# board.net
KiCad netlist of a schematic drawn in EAGLE
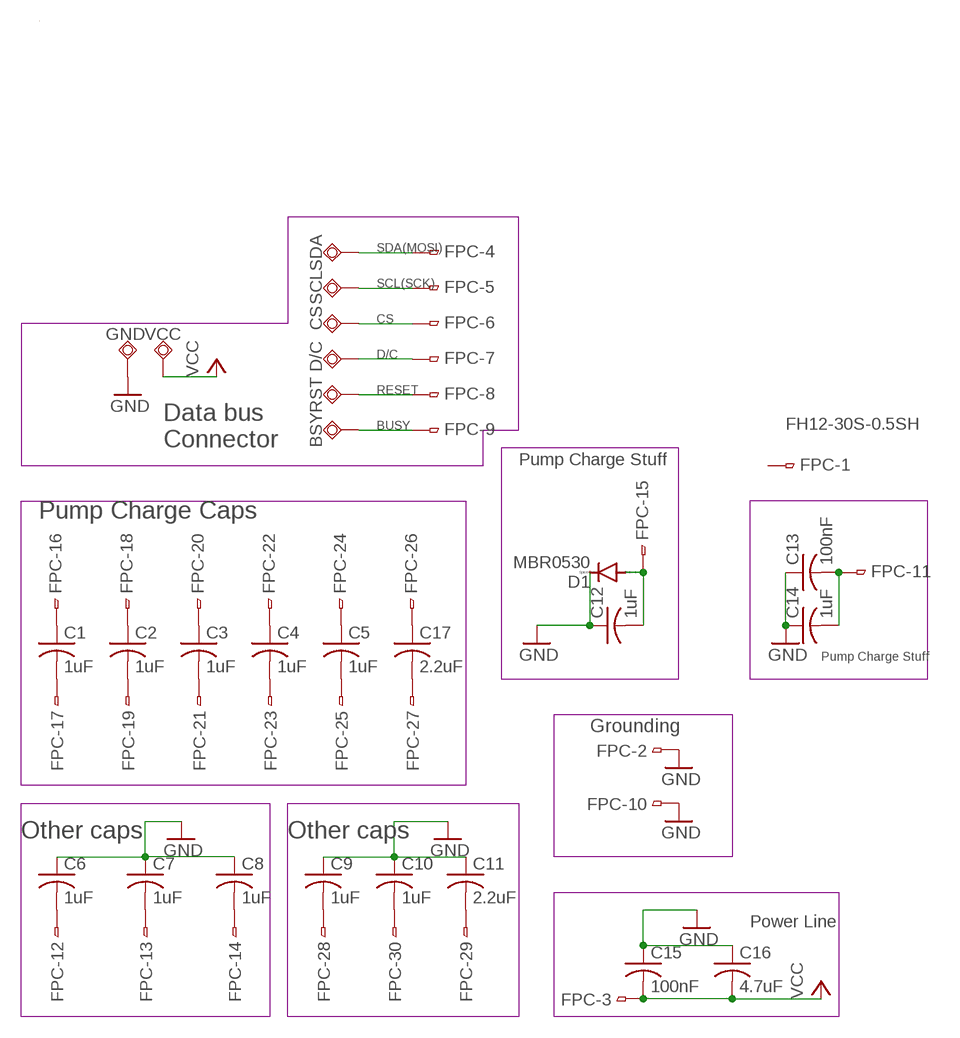
[diagram p0: schematic, sheet 1]

(export (version "E")
  (design (tool "Eeschema 10.0.6"))
  (components
    (comp (ref "BSY")
      (value "TPSQTP18SQ")
      (footprint "eagle-import:TP18SQ")
      (libsource (lib "eagle-import") (part "TPSQTP18SQ"))
    )
    (comp (ref "C1")
      (value "1uF")
      (footprint "eagle-import:C0805")
      (libsource (lib "eagle-import") (part "C-USC0805"))
    )
    (comp (ref "C2")
      (value "1uF")
      (footprint "eagle-import:C0805")
      (libsource (lib "eagle-import") (part "C-USC0805"))
    )
    (comp (ref "C3")
      (value "1uF")
      (footprint "eagle-import:C0805")
      (libsource (lib "eagle-import") (part "C-USC0805"))
    )
    (comp (ref "C4")
      (value "1uF")
      (footprint "eagle-import:C0805")
      (libsource (lib "eagle-import") (part "C-USC0805"))
    )
    (comp (ref "C5")
      (value "1uF")
      (footprint "eagle-import:C0805")
      (libsource (lib "eagle-import") (part "C-USC0805"))
    )
    (comp (ref "C6")
      (value "1uF")
      (footprint "eagle-import:C0805")
      (libsource (lib "eagle-import") (part "C-USC0805"))
    )
    (comp (ref "C7")
      (value "1uF")
      (footprint "eagle-import:C0805")
      (libsource (lib "eagle-import") (part "C-USC0805"))
    )
    (comp (ref "C8")
      (value "1uF")
      (footprint "eagle-import:C0805")
      (libsource (lib "eagle-import") (part "C-USC0805"))
    )
    (comp (ref "C9")
      (value "1uF")
      (footprint "eagle-import:C0805")
      (libsource (lib "eagle-import") (part "C-USC0805"))
    )
    (comp (ref "C10")
      (value "1uF")
      (footprint "eagle-import:C0805")
      (libsource (lib "eagle-import") (part "C-USC0805"))
    )
    (comp (ref "C11")
      (value "2.2uF")
      (footprint "eagle-import:C1206")
      (libsource (lib "eagle-import") (part "C-USC1206"))
    )
    (comp (ref "C12")
      (value "1uF")
      (footprint "eagle-import:C0805")
      (libsource (lib "eagle-import") (part "C-USC0805"))
    )
    (comp (ref "C13")
      (value "100nF")
      (footprint "eagle-import:C0805")
      (libsource (lib "eagle-import") (part "C-USC0805"))
    )
    (comp (ref "C14")
      (value "1uF")
      (footprint "eagle-import:C0805")
      (libsource (lib "eagle-import") (part "C-USC0805"))
    )
    (comp (ref "C15")
      (value "100nF")
      (footprint "eagle-import:C0805")
      (libsource (lib "eagle-import") (part "C-USC0805"))
    )
    (comp (ref "C16")
      (value "4.7uF")
      (footprint "eagle-import:C0805")
      (libsource (lib "eagle-import") (part "C-USC0805"))
    )
    (comp (ref "C17")
      (value "2.2uF")
      (footprint "eagle-import:C1206")
      (libsource (lib "eagle-import") (part "C-USC1206"))
    )
    (comp (ref "CS")
      (value "TPSQTP18SQ")
      (footprint "eagle-import:TP18SQ")
      (libsource (lib "eagle-import") (part "TPSQTP18SQ"))
    )
    (comp (ref "D/C")
      (value "TPSQTP18SQ")
      (footprint "eagle-import:TP18SQ")
      (libsource (lib "eagle-import") (part "TPSQTP18SQ"))
    )
    (comp (ref "D1")
      (value "MBR0530")
      (footprint "eagle-import:SOD-123_MINI-SMA")
      (libsource (lib "eagle-import") (part "CGRM400-G1"))
    )
    (comp (ref "FPC")
      (value "FH12-30S-0.5SH")
      (footprint "eagle-import:FH12-30S-0.5SH")
      (fields (field (name "MPN") "FH12-30S-0.5SH(55)"))
      (libsource (lib "eagle-import") (part "FH12-30S-0.5SH"))
    )
    (comp (ref "GND")
      (value "TPSQTP18SQ")
      (footprint "eagle-import:TP18SQ")
      (libsource (lib "eagle-import") (part "TPSQTP18SQ"))
    )
    (comp (ref "RST")
      (value "TPSQTP18SQ")
      (footprint "eagle-import:TP18SQ")
      (libsource (lib "eagle-import") (part "TPSQTP18SQ"))
    )
    (comp (ref "SCL")
      (value "TPSQTP18SQ")
      (footprint "eagle-import:TP18SQ")
      (libsource (lib "eagle-import") (part "TPSQTP18SQ"))
    )
    (comp (ref "SDA")
      (value "TPSQTP18SQ")
      (footprint "eagle-import:TP18SQ")
      (libsource (lib "eagle-import") (part "TPSQTP18SQ"))
    )
    (comp (ref "VCC")
      (value "TPSQTP18SQ")
      (footprint "eagle-import:TP18SQ")
      (libsource (lib "eagle-import") (part "TPSQTP18SQ"))
    )
  )
  (nets
    (net (code "1") (name "/BUSY") (class "Default")
      (node (ref "BSY") (pin "TP") (pinfunction "TP_TP") (pintype "input"))
      (node (ref "FPC") (pin "9") (pinfunction "1_9") (pintype "passive"))
    )
    (net (code "2") (name "/CS") (class "Default")
      (node (ref "CS") (pin "TP") (pinfunction "TP_TP") (pintype "input"))
      (node (ref "FPC") (pin "6") (pinfunction "1_6") (pintype "passive"))
    )
    (net (code "3") (name "/D{slash}C") (class "Default")
      (node (ref "D/C") (pin "TP") (pinfunction "TP_TP") (pintype "input"))
      (node (ref "FPC") (pin "7") (pinfunction "1_7") (pintype "passive"))
    )
    (net (code "4") (name "/RESET") (class "Default")
      (node (ref "FPC") (pin "8") (pinfunction "1_8") (pintype "passive"))
      (node (ref "RST") (pin "TP") (pinfunction "TP_TP") (pintype "input"))
    )
    (net (code "5") (name "/SCL(SCK)") (class "Default")
      (node (ref "FPC") (pin "5") (pinfunction "1_5") (pintype "passive"))
      (node (ref "SCL") (pin "TP") (pinfunction "TP_TP") (pintype "input"))
    )
    (net (code "6") (name "/SDA(MOSI)") (class "Default")
      (node (ref "FPC") (pin "4") (pinfunction "1_4") (pintype "passive"))
      (node (ref "SDA") (pin "TP") (pinfunction "TP_TP") (pintype "input"))
    )
    (net (code "7") (name "GND") (class "Default")
      (node (ref "C10") (pin "1") (pinfunction "1_1") (pintype "passive"))
      (node (ref "C11") (pin "1") (pinfunction "1_1") (pintype "passive"))
      (node (ref "C12") (pin "1") (pinfunction "1_1") (pintype "passive"))
      (node (ref "C13") (pin "1") (pinfunction "1_1") (pintype "passive"))
      (node (ref "C14") (pin "1") (pinfunction "1_1") (pintype "passive"))
      (node (ref "C15") (pin "1") (pinfunction "1_1") (pintype "passive"))
      (node (ref "C16") (pin "1") (pinfunction "1_1") (pintype "passive"))
      (node (ref "C6") (pin "1") (pinfunction "1_1") (pintype "passive"))
      (node (ref "C7") (pin "1") (pinfunction "1_1") (pintype "passive"))
      (node (ref "C8") (pin "1") (pinfunction "1_1") (pintype "passive"))
      (node (ref "C9") (pin "1") (pinfunction "1_1") (pintype "passive"))
      (node (ref "D1") (pin "C") (pinfunction "C_C") (pintype "passive"))
      (node (ref "FPC") (pin "10") (pinfunction "1_10") (pintype "passive"))
      (node (ref "FPC") (pin "2") (pinfunction "1_2") (pintype "passive"))
      (node (ref "GND") (pin "TP") (pinfunction "TP_TP") (pintype "input"))
    )
    (net (code "8") (name "Net-(FPCC-1)") (class "Default")
      (node (ref "C13") (pin "2") (pinfunction "2_2") (pintype "passive"))
      (node (ref "C14") (pin "2") (pinfunction "2_2") (pintype "passive"))
      (node (ref "FPC") (pin "11") (pinfunction "1_11") (pintype "passive"))
    )
    (net (code "9") (name "Net-(FPCD-1)") (class "Default")
      (node (ref "C6") (pin "2") (pinfunction "2_2") (pintype "passive"))
      (node (ref "FPC") (pin "12") (pinfunction "1_12") (pintype "passive"))
    )
    (net (code "10") (name "Net-(FPCE-1)") (class "Default")
      (node (ref "C7") (pin "2") (pinfunction "2_2") (pintype "passive"))
      (node (ref "FPC") (pin "13") (pinfunction "1_13") (pintype "passive"))
    )
    (net (code "11") (name "Net-(FPCF-1)") (class "Default")
      (node (ref "C8") (pin "2") (pinfunction "2_2") (pintype "passive"))
      (node (ref "FPC") (pin "14") (pinfunction "1_14") (pintype "passive"))
    )
    (net (code "12") (name "Net-(FPCG-1)") (class "Default")
      (node (ref "C12") (pin "2") (pinfunction "2_2") (pintype "passive"))
      (node (ref "D1") (pin "A") (pinfunction "A_A") (pintype "passive"))
      (node (ref "FPC") (pin "15") (pinfunction "1_15") (pintype "passive"))
    )
    (net (code "13") (name "Net-(FPCH-1)") (class "Default")
      (node (ref "C1") (pin "1") (pinfunction "1_1") (pintype "passive"))
      (node (ref "FPC") (pin "16") (pinfunction "1_16") (pintype "passive"))
    )
    (net (code "14") (name "Net-(FPCI-1)") (class "Default")
      (node (ref "C1") (pin "2") (pinfunction "2_2") (pintype "passive"))
      (node (ref "FPC") (pin "17") (pinfunction "1_17") (pintype "passive"))
    )
    (net (code "15") (name "Net-(FPCJ-1)") (class "Default")
      (node (ref "C2") (pin "1") (pinfunction "1_1") (pintype "passive"))
      (node (ref "FPC") (pin "18") (pinfunction "1_18") (pintype "passive"))
    )
    (net (code "16") (name "Net-(FPCK-1)") (class "Default")
      (node (ref "C2") (pin "2") (pinfunction "2_2") (pintype "passive"))
      (node (ref "FPC") (pin "19") (pinfunction "1_19") (pintype "passive"))
    )
    (net (code "17") (name "Net-(FPCM-1)") (class "Default")
      (node (ref "C3") (pin "1") (pinfunction "1_1") (pintype "passive"))
      (node (ref "FPC") (pin "20") (pinfunction "1_20") (pintype "passive"))
    )
    (net (code "18") (name "Net-(FPCN-1)") (class "Default")
      (node (ref "C3") (pin "2") (pinfunction "2_2") (pintype "passive"))
      (node (ref "FPC") (pin "21") (pinfunction "1_21") (pintype "passive"))
    )
    (net (code "19") (name "Net-(FPCO-1)") (class "Default")
      (node (ref "C4") (pin "1") (pinfunction "1_1") (pintype "passive"))
      (node (ref "FPC") (pin "22") (pinfunction "1_22") (pintype "passive"))
    )
    (net (code "20") (name "Net-(FPCP-1)") (class "Default")
      (node (ref "C4") (pin "2") (pinfunction "2_2") (pintype "passive"))
      (node (ref "FPC") (pin "23") (pinfunction "1_23") (pintype "passive"))
    )
    (net (code "21") (name "Net-(FPCQ-1)") (class "Default")
      (node (ref "C5") (pin "1") (pinfunction "1_1") (pintype "passive"))
      (node (ref "FPC") (pin "24") (pinfunction "1_24") (pintype "passive"))
    )
    (net (code "22") (name "Net-(FPCR-1)") (class "Default")
      (node (ref "C5") (pin "2") (pinfunction "2_2") (pintype "passive"))
      (node (ref "FPC") (pin "25") (pinfunction "1_25") (pintype "passive"))
    )
    (net (code "23") (name "Net-(FPCS-1)") (class "Default")
      (node (ref "C17") (pin "1") (pinfunction "1_1") (pintype "passive"))
      (node (ref "FPC") (pin "26") (pinfunction "1_26") (pintype "passive"))
    )
    (net (code "24") (name "Net-(FPCT-1)") (class "Default")
      (node (ref "C17") (pin "2") (pinfunction "2_2") (pintype "passive"))
      (node (ref "FPC") (pin "27") (pinfunction "1_27") (pintype "passive"))
    )
    (net (code "25") (name "Net-(FPCU-1)") (class "Default")
      (node (ref "C9") (pin "2") (pinfunction "2_2") (pintype "passive"))
      (node (ref "FPC") (pin "28") (pinfunction "1_28") (pintype "passive"))
    )
    (net (code "26") (name "Net-(FPCV-1)") (class "Default")
      (node (ref "C11") (pin "2") (pinfunction "2_2") (pintype "passive"))
      (node (ref "FPC") (pin "29") (pinfunction "1_29") (pintype "passive"))
    )
    (net (code "27") (name "Net-(FPCX-1)") (class "Default")
      (node (ref "C10") (pin "2") (pinfunction "2_2") (pintype "passive"))
      (node (ref "FPC") (pin "30") (pinfunction "1_30") (pintype "passive"))
    )
    (net (code "28") (name "VCC") (class "Default")
      (node (ref "C15") (pin "2") (pinfunction "2_2") (pintype "passive"))
      (node (ref "C16") (pin "2") (pinfunction "2_2") (pintype "passive"))
      (node (ref "FPC") (pin "3") (pinfunction "1_3") (pintype "passive"))
      (node (ref "VCC") (pin "TP") (pinfunction "TP_TP") (pintype "input"))
    )
    (net (code "29") (name "unconnected-(FPC-Pad1)") (class "Default")
      (node (ref "FPC") (pin "1") (pinfunction "1_1") (pintype "passive"))
    )
  )
)
